# Sensor_Board_0xXX_Prototyping_v1.net
KiCad netlist of a schematic drawn in EAGLE
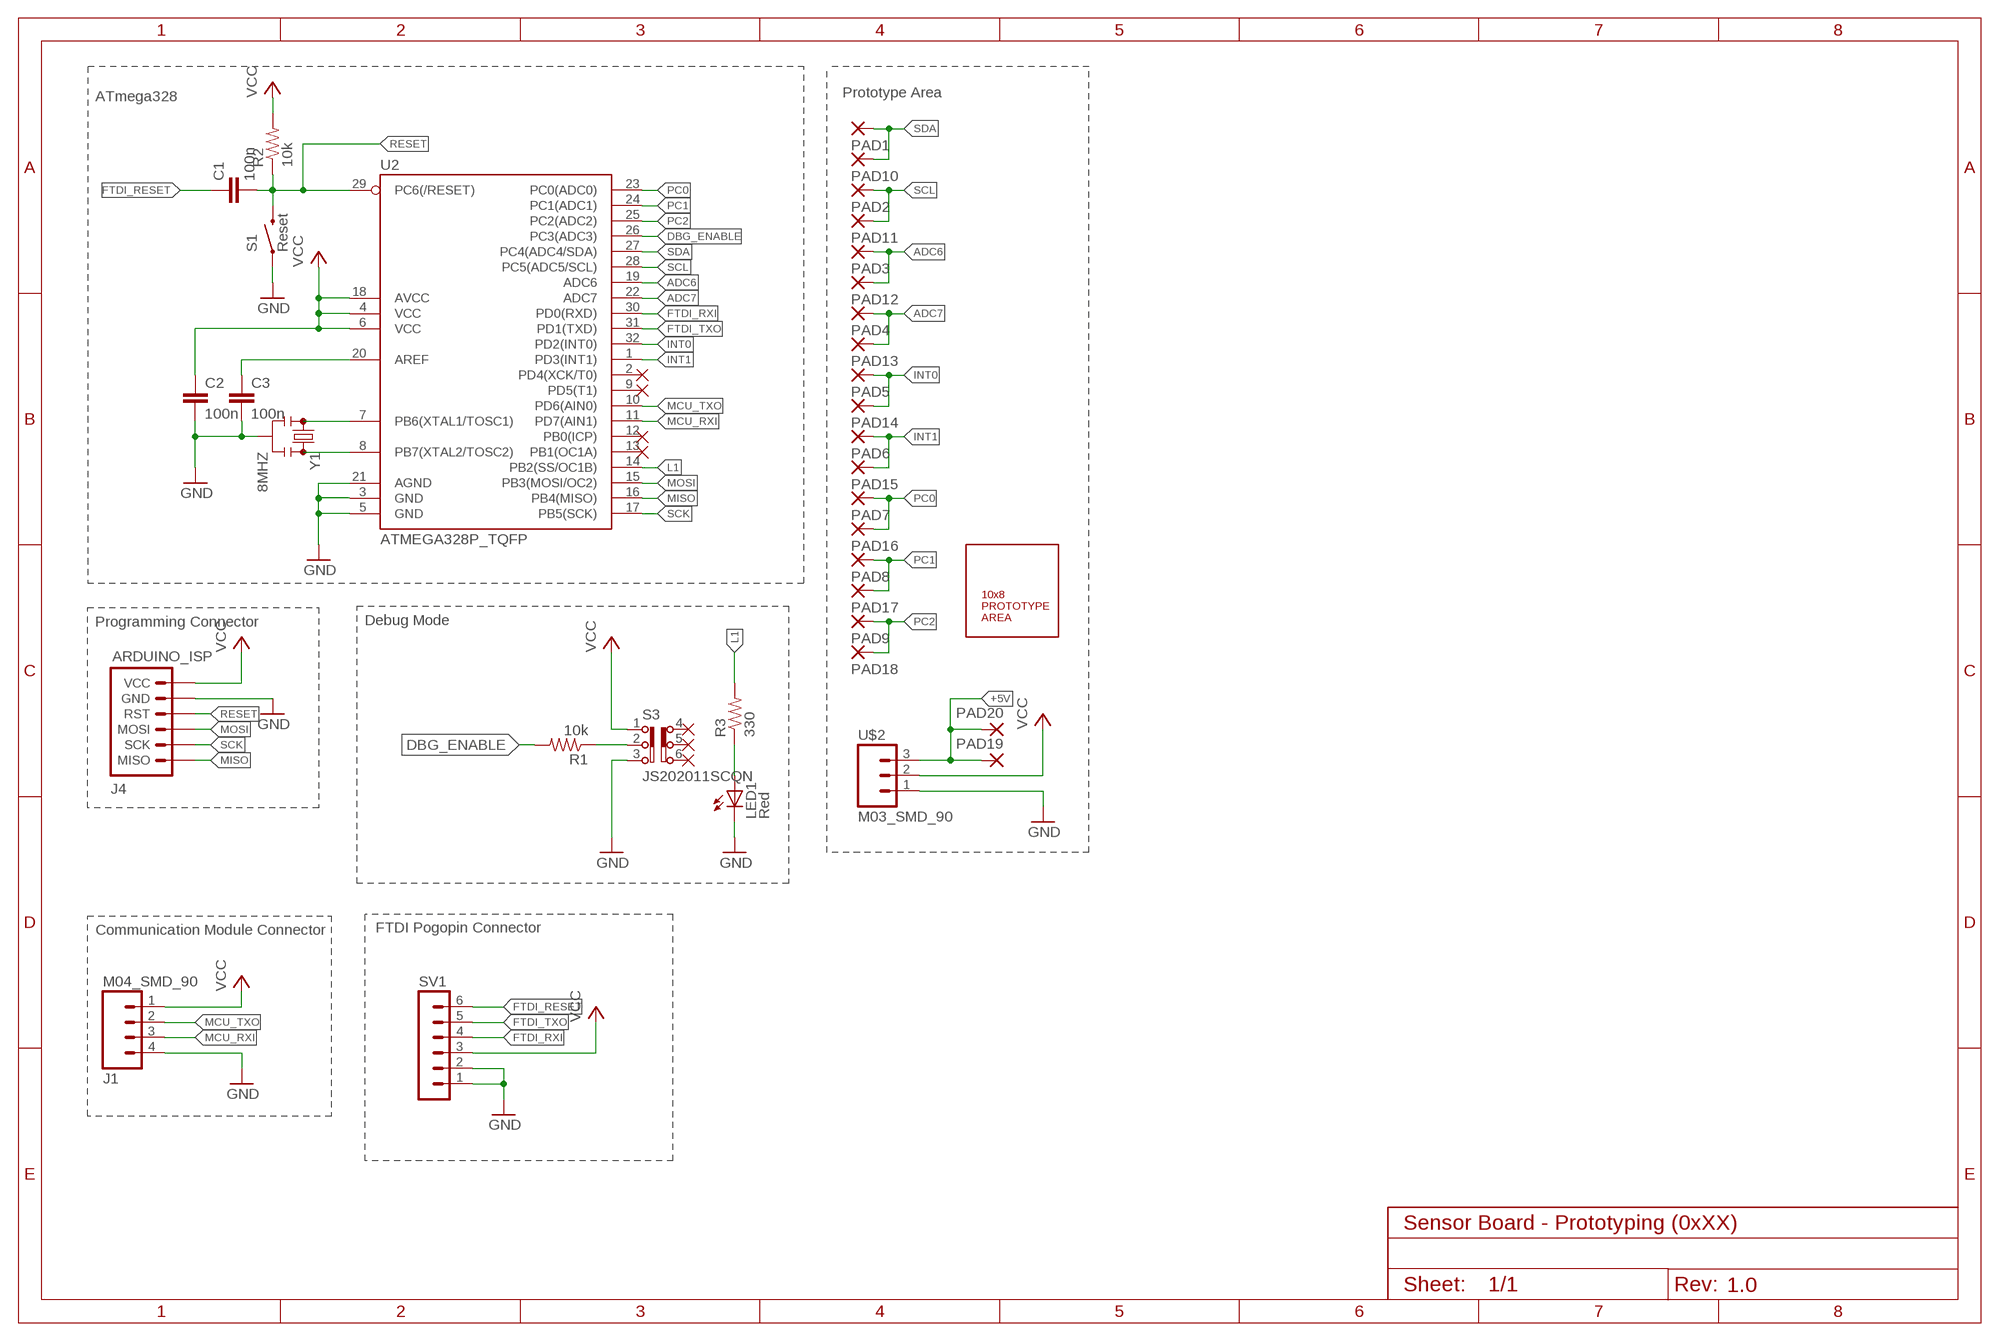
[diagram p0: schematic, sheet 1]

(export (version "E")
  (design (tool "Eeschema 10.0.6"))
  (components
    (comp (ref "C1")
      (value "100n")
      (footprint "eagle-import:C0805")
      (libsource (lib "eagle-import") (part "C"))
    )
    (comp (ref "C2")
      (value "100n")
      (footprint "eagle-import:C0805")
      (libsource (lib "eagle-import") (part "C"))
    )
    (comp (ref "C3")
      (value "100n")
      (footprint "eagle-import:C0805")
      (libsource (lib "eagle-import") (part "C"))
    )
    (comp (ref "J1")
      (value "M04_SMD_90")
      (footprint "eagle-import:M04_SMD_90")
      (libsource (lib "eagle-import") (part "M04_SMD_90"))
    )
    (comp (ref "J4")
      (value "ARDUINO_ISP")
      (footprint "eagle-import:M-2X3")
      (libsource (lib "eagle-import") (part "ARDUINO_ISP"))
    )
    (comp (ref "LED1")
      (value "Red")
      (footprint "eagle-import:SML0805")
      (libsource (lib "eagle-import") (part "LEDSML0805"))
    )
    (comp (ref "PAD1")
      (value "1,6/0,9")
      (footprint "eagle-import:1,6_0,9")
      (libsource (lib "eagle-import") (part "1,6/0,9"))
    )
    (comp (ref "PAD2")
      (value "1,6/0,9")
      (footprint "eagle-import:1,6_0,9")
      (libsource (lib "eagle-import") (part "1,6/0,9"))
    )
    (comp (ref "PAD3")
      (value "1,6/0,9")
      (footprint "eagle-import:1,6_0,9")
      (libsource (lib "eagle-import") (part "1,6/0,9"))
    )
    (comp (ref "PAD4")
      (value "1,6/0,9")
      (footprint "eagle-import:1,6_0,9")
      (libsource (lib "eagle-import") (part "1,6/0,9"))
    )
    (comp (ref "PAD5")
      (value "1,6/0,9")
      (footprint "eagle-import:1,6_0,9")
      (libsource (lib "eagle-import") (part "1,6/0,9"))
    )
    (comp (ref "PAD6")
      (value "1,6/0,9")
      (footprint "eagle-import:1,6_0,9")
      (libsource (lib "eagle-import") (part "1,6/0,9"))
    )
    (comp (ref "PAD7")
      (value "1,6/0,9")
      (footprint "eagle-import:1,6_0,9")
      (libsource (lib "eagle-import") (part "1,6/0,9"))
    )
    (comp (ref "PAD8")
      (value "1,6/0,9")
      (footprint "eagle-import:1,6_0,9")
      (libsource (lib "eagle-import") (part "1,6/0,9"))
    )
    (comp (ref "PAD9")
      (value "1,6/0,9")
      (footprint "eagle-import:1,6_0,9")
      (libsource (lib "eagle-import") (part "1,6/0,9"))
    )
    (comp (ref "PAD10")
      (value "1,6/0,9")
      (footprint "eagle-import:1,6_0,9")
      (libsource (lib "eagle-import") (part "1,6/0,9"))
    )
    (comp (ref "PAD11")
      (value "1,6/0,9")
      (footprint "eagle-import:1,6_0,9")
      (libsource (lib "eagle-import") (part "1,6/0,9"))
    )
    (comp (ref "PAD12")
      (value "1,6/0,9")
      (footprint "eagle-import:1,6_0,9")
      (libsource (lib "eagle-import") (part "1,6/0,9"))
    )
    (comp (ref "PAD13")
      (value "1,6/0,9")
      (footprint "eagle-import:1,6_0,9")
      (libsource (lib "eagle-import") (part "1,6/0,9"))
    )
    (comp (ref "PAD14")
      (value "1,6/0,9")
      (footprint "eagle-import:1,6_0,9")
      (libsource (lib "eagle-import") (part "1,6/0,9"))
    )
    (comp (ref "PAD15")
      (value "1,6/0,9")
      (footprint "eagle-import:1,6_0,9")
      (libsource (lib "eagle-import") (part "1,6/0,9"))
    )
    (comp (ref "PAD16")
      (value "1,6/0,9")
      (footprint "eagle-import:1,6_0,9")
      (libsource (lib "eagle-import") (part "1,6/0,9"))
    )
    (comp (ref "PAD17")
      (value "1,6/0,9")
      (footprint "eagle-import:1,6_0,9")
      (libsource (lib "eagle-import") (part "1,6/0,9"))
    )
    (comp (ref "PAD18")
      (value "1,6/0,9")
      (footprint "eagle-import:1,6_0,9")
      (libsource (lib "eagle-import") (part "1,6/0,9"))
    )
    (comp (ref "PAD19")
      (value "1,6/0,9")
      (footprint "eagle-import:1,6_0,9")
      (libsource (lib "eagle-import") (part "1,6/0,9"))
    )
    (comp (ref "PAD20")
      (value "1,6/0,9")
      (footprint "eagle-import:1,6_0,9")
      (libsource (lib "eagle-import") (part "1,6/0,9"))
    )
    (comp (ref "R1")
      (value "10k")
      (footprint "eagle-import:0805")
      (libsource (lib "eagle-import") (part "RESISTOR0805-RES"))
    )
    (comp (ref "R2")
      (value "10k")
      (footprint "eagle-import:0805")
      (libsource (lib "eagle-import") (part "RESISTOR0805-RES"))
    )
    (comp (ref "R3")
      (value "330")
      (footprint "eagle-import:0805")
      (libsource (lib "eagle-import") (part "RESISTOR0805-RES"))
    )
    (comp (ref "S1")
      (value "Reset")
      (footprint "eagle-import:M-PUSHBUTTON-SMD")
      (libsource (lib "eagle-import") (part "PUSHBUTTON"))
    )
    (comp (ref "S3")
      (value "JS202011SCQN")
      (footprint "eagle-import:JS202011SCQN")
      (libsource (lib "eagle-import") (part "JS202011SCQN"))
    )
    (comp (ref "SV1")
      (value "MA06-1")
      (footprint "eagle-import:MA06-1")
      (libsource (lib "eagle-import") (part "MA06-1"))
    )
    (comp (ref "U$1")
      (value "10X8_PROTOTYPE_AREA")
      (footprint "eagle-import:10X8_PROTOTYPE_AREA")
      (libsource (lib "eagle-import") (part "10X8_PROTOTYPE_AREA"))
    )
    (comp (ref "U$2")
      (value "M03_SMD_90")
      (footprint "eagle-import:M03_SMD_90")
      (libsource (lib "eagle-import") (part "M03_SMD_90"))
    )
    (comp (ref "U2")
      (value "ATMEGA328P_TQFP")
      (footprint "eagle-import:TQFP32-08")
      (libsource (lib "eagle-import") (part "ATMEGA328P_TQFP"))
    )
    (comp (ref "Y1")
      (value "8MHZ")
      (footprint "eagle-import:RESONATOR-SMD")
      (libsource (lib "eagle-import") (part "RESONATOR8MHZ"))
    )
  )
  (nets
    (net (code "1") (name "+5V") (class "Default")
      (node (ref "PAD19") (pin "1") (pinfunction "P_1") (pintype "passive"))
      (node (ref "PAD20") (pin "1") (pinfunction "P_1") (pintype "passive"))
      (node (ref "U$2") (pin "3") (pinfunction "3_3") (pintype "passive"))
    )
    (net (code "2") (name "ADC6") (class "Default")
      (node (ref "PAD12") (pin "1") (pinfunction "P_1") (pintype "passive"))
      (node (ref "PAD3") (pin "1") (pinfunction "P_1") (pintype "passive"))
      (node (ref "U2") (pin "19") (pinfunction "ADC6_19") (pintype "bidirectional"))
    )
    (net (code "3") (name "ADC7") (class "Default")
      (node (ref "PAD13") (pin "1") (pinfunction "P_1") (pintype "passive"))
      (node (ref "PAD4") (pin "1") (pinfunction "P_1") (pintype "passive"))
      (node (ref "U2") (pin "22") (pinfunction "ADC7_22") (pintype "bidirectional"))
    )
    (net (code "4") (name "DBG_ENABLE") (class "Default")
      (node (ref "R1") (pin "2") (pinfunction "2_2") (pintype "passive"))
      (node (ref "U2") (pin "26") (pinfunction "PC3(ADC3)_26") (pintype "bidirectional"))
    )
    (net (code "5") (name "FTDI_RESET") (class "Default")
      (node (ref "C1") (pin "1") (pinfunction "1_1") (pintype "passive"))
      (node (ref "SV1") (pin "6") (pinfunction "6_6") (pintype "passive"))
    )
    (net (code "6") (name "FTDI_RXI") (class "Default")
      (node (ref "SV1") (pin "4") (pinfunction "4_4") (pintype "passive"))
      (node (ref "U2") (pin "30") (pinfunction "PD0(RXD)_30") (pintype "bidirectional"))
    )
    (net (code "7") (name "FTDI_TXO") (class "Default")
      (node (ref "SV1") (pin "5") (pinfunction "5_5") (pintype "passive"))
      (node (ref "U2") (pin "31") (pinfunction "PD1(TXD)_31") (pintype "bidirectional"))
    )
    (net (code "8") (name "GND") (class "Default")
      (node (ref "C2") (pin "2") (pinfunction "2_2") (pintype "passive"))
      (node (ref "C3") (pin "2") (pinfunction "2_2") (pintype "passive"))
      (node (ref "J1") (pin "4") (pinfunction "4_4") (pintype "passive"))
      (node (ref "J4") (pin "P$5") (pinfunction "GND_P$5") (pintype "passive"))
      (node (ref "LED1") (pin "C") (pinfunction "C_C") (pintype "passive"))
      (node (ref "S1") (pin "1") (pinfunction "LEFT_1") (pintype "passive"))
      (node (ref "S1") (pin "2") (pinfunction "LEFT_2") (pintype "passive"))
      (node (ref "S3") (pin "3") (pinfunction "3_3") (pintype "passive"))
      (node (ref "SV1") (pin "1") (pinfunction "1_1") (pintype "passive"))
      (node (ref "SV1") (pin "2") (pinfunction "2_2") (pintype "passive"))
      (node (ref "U$2") (pin "1") (pinfunction "1_1") (pintype "passive"))
      (node (ref "U2") (pin "21") (pinfunction "AGND_21") (pintype "bidirectional"))
      (node (ref "U2") (pin "3") (pinfunction "GND_3") (pintype "bidirectional"))
      (node (ref "U2") (pin "5") (pinfunction "GND_5") (pintype "bidirectional"))
      (node (ref "Y1") (pin "2") (pinfunction "2_2") (pintype "passive"))
    )
    (net (code "9") (name "INT0") (class "Default")
      (node (ref "PAD14") (pin "1") (pinfunction "P_1") (pintype "passive"))
      (node (ref "PAD5") (pin "1") (pinfunction "P_1") (pintype "passive"))
      (node (ref "U2") (pin "32") (pinfunction "PD2(INT0)_32") (pintype "bidirectional"))
    )
    (net (code "10") (name "INT1") (class "Default")
      (node (ref "PAD15") (pin "1") (pinfunction "P_1") (pintype "passive"))
      (node (ref "PAD6") (pin "1") (pinfunction "P_1") (pintype "passive"))
      (node (ref "U2") (pin "1") (pinfunction "PD3(INT1)_1") (pintype "bidirectional"))
    )
    (net (code "11") (name "L1") (class "Default")
      (node (ref "R3") (pin "2") (pinfunction "2_2") (pintype "passive"))
      (node (ref "U2") (pin "14") (pinfunction "PB2(SS/OC1B)_14") (pintype "bidirectional"))
    )
    (net (code "12") (name "MCU_RXI") (class "Default")
      (node (ref "J1") (pin "3") (pinfunction "3_3") (pintype "passive"))
      (node (ref "U2") (pin "11") (pinfunction "PD7(AIN1)_11") (pintype "bidirectional"))
    )
    (net (code "13") (name "MCU_TXO") (class "Default")
      (node (ref "J1") (pin "2") (pinfunction "2_2") (pintype "passive"))
      (node (ref "U2") (pin "10") (pinfunction "PD6(AIN0)_10") (pintype "bidirectional"))
    )
    (net (code "14") (name "MISO") (class "Default")
      (node (ref "J4") (pin "P$1") (pinfunction "MISO_P$1") (pintype "passive"))
      (node (ref "U2") (pin "16") (pinfunction "PB4(MISO)_16") (pintype "bidirectional"))
    )
    (net (code "15") (name "MOSI") (class "Default")
      (node (ref "J4") (pin "P$3") (pinfunction "MOSI_P$3") (pintype "passive"))
      (node (ref "U2") (pin "15") (pinfunction "PB3(MOSI/OC2)_15") (pintype "bidirectional"))
    )
    (net (code "16") (name "Net-(LED1-PadA)") (class "Default")
      (node (ref "LED1") (pin "A") (pinfunction "A_A") (pintype "passive"))
      (node (ref "R3") (pin "1") (pinfunction "1_1") (pintype "passive"))
    )
    (net (code "17") (name "Net-(R1-Pad1)") (class "Default")
      (node (ref "R1") (pin "1") (pinfunction "1_1") (pintype "passive"))
      (node (ref "S3") (pin "2") (pinfunction "2_2") (pintype "passive"))
    )
    (net (code "18") (name "Net-(U2-AREF)") (class "Default")
      (node (ref "C3") (pin "1") (pinfunction "1_1") (pintype "passive"))
      (node (ref "U2") (pin "20") (pinfunction "AREF_20") (pintype "bidirectional"))
    )
    (net (code "19") (name "Net-(U2-PB6(XTAL1{slash}TOSC1))") (class "Default")
      (node (ref "U2") (pin "7") (pinfunction "PB6(XTAL1/TOSC1)_7") (pintype "bidirectional"))
      (node (ref "Y1") (pin "1") (pinfunction "1_1") (pintype "passive"))
    )
    (net (code "20") (name "Net-(U2-PB7(XTAL2{slash}TOSC2))") (class "Default")
      (node (ref "U2") (pin "8") (pinfunction "PB7(XTAL2/TOSC2)_8") (pintype "bidirectional"))
      (node (ref "Y1") (pin "3") (pinfunction "3_3") (pintype "passive"))
    )
    (net (code "21") (name "PC0") (class "Default")
      (node (ref "PAD16") (pin "1") (pinfunction "P_1") (pintype "passive"))
      (node (ref "PAD7") (pin "1") (pinfunction "P_1") (pintype "passive"))
      (node (ref "U2") (pin "23") (pinfunction "PC0(ADC0)_23") (pintype "bidirectional"))
    )
    (net (code "22") (name "PC1") (class "Default")
      (node (ref "PAD17") (pin "1") (pinfunction "P_1") (pintype "passive"))
      (node (ref "PAD8") (pin "1") (pinfunction "P_1") (pintype "passive"))
      (node (ref "U2") (pin "24") (pinfunction "PC1(ADC1)_24") (pintype "bidirectional"))
    )
    (net (code "23") (name "PC2") (class "Default")
      (node (ref "PAD18") (pin "1") (pinfunction "P_1") (pintype "passive"))
      (node (ref "PAD9") (pin "1") (pinfunction "P_1") (pintype "passive"))
      (node (ref "U2") (pin "25") (pinfunction "PC2(ADC2)_25") (pintype "bidirectional"))
    )
    (net (code "24") (name "RESET") (class "Default")
      (node (ref "C1") (pin "2") (pinfunction "2_2") (pintype "passive"))
      (node (ref "J4") (pin "P$4") (pinfunction "RST_P$4") (pintype "passive"))
      (node (ref "R2") (pin "1") (pinfunction "1_1") (pintype "passive"))
      (node (ref "S1") (pin "3") (pinfunction "RIGHT_3") (pintype "passive"))
      (node (ref "S1") (pin "4") (pinfunction "RIGHT_4") (pintype "passive"))
      (node (ref "U2") (pin "29") (pinfunction "PC6(/RESET)_29") (pintype "bidirectional"))
    )
    (net (code "25") (name "SCK") (class "Default")
      (node (ref "J4") (pin "P$2") (pinfunction "SCK_P$2") (pintype "passive"))
      (node (ref "U2") (pin "17") (pinfunction "PB5(SCK)_17") (pintype "bidirectional"))
    )
    (net (code "26") (name "SCL") (class "Default")
      (node (ref "PAD11") (pin "1") (pinfunction "P_1") (pintype "passive"))
      (node (ref "PAD2") (pin "1") (pinfunction "P_1") (pintype "passive"))
      (node (ref "U2") (pin "28") (pinfunction "PC5(ADC5/SCL)_28") (pintype "bidirectional"))
    )
    (net (code "27") (name "SDA") (class "Default")
      (node (ref "PAD1") (pin "1") (pinfunction "P_1") (pintype "passive"))
      (node (ref "PAD10") (pin "1") (pinfunction "P_1") (pintype "passive"))
      (node (ref "U2") (pin "27") (pinfunction "PC4(ADC4/SDA)_27") (pintype "bidirectional"))
    )
    (net (code "28") (name "VCC") (class "Default")
      (node (ref "C2") (pin "1") (pinfunction "1_1") (pintype "passive"))
      (node (ref "J1") (pin "1") (pinfunction "1_1") (pintype "passive"))
      (node (ref "J4") (pin "P$6") (pinfunction "VCC_P$6") (pintype "passive"))
      (node (ref "R2") (pin "2") (pinfunction "2_2") (pintype "passive"))
      (node (ref "S3") (pin "1") (pinfunction "1_1") (pintype "passive"))
      (node (ref "SV1") (pin "3") (pinfunction "3_3") (pintype "passive"))
      (node (ref "U$2") (pin "2") (pinfunction "2_2") (pintype "passive"))
      (node (ref "U2") (pin "18") (pinfunction "AVCC_18") (pintype "bidirectional"))
      (node (ref "U2") (pin "4") (pinfunction "VCC_4") (pintype "bidirectional"))
      (node (ref "U2") (pin "6") (pinfunction "VCC_6") (pintype "bidirectional"))
    )
    (net (code "29") (name "unconnected-(S3-Pad4)") (class "Default")
      (node (ref "S3") (pin "4") (pinfunction "4_4") (pintype "passive"))
    )
    (net (code "30") (name "unconnected-(S3-Pad5)") (class "Default")
      (node (ref "S3") (pin "5") (pinfunction "5_5") (pintype "passive"))
    )
    (net (code "31") (name "unconnected-(S3-Pad6)") (class "Default")
      (node (ref "S3") (pin "6") (pinfunction "6_6") (pintype "passive"))
    )
    (net (code "32") (name "unconnected-(U2-PB0(ICP)-Pad12)") (class "Default")
      (node (ref "U2") (pin "12") (pinfunction "PB0(ICP)_12") (pintype "bidirectional"))
    )
    (net (code "33") (name "unconnected-(U2-PB1(OC1A)-Pad13)") (class "Default")
      (node (ref "U2") (pin "13") (pinfunction "PB1(OC1A)_13") (pintype "bidirectional"))
    )
    (net (code "34") (name "unconnected-(U2-PD4(XCK{slash}T0)-Pad2)") (class "Default")
      (node (ref "U2") (pin "2") (pinfunction "PD4(XCK/T0)_2") (pintype "bidirectional"))
    )
    (net (code "35") (name "unconnected-(U2-PD5(T1)-Pad9)") (class "Default")
      (node (ref "U2") (pin "9") (pinfunction "PD5(T1)_9") (pintype "bidirectional"))
    )
  )
)
